# design.net
KiCad netlist of a schematic drawn in Altium Designer
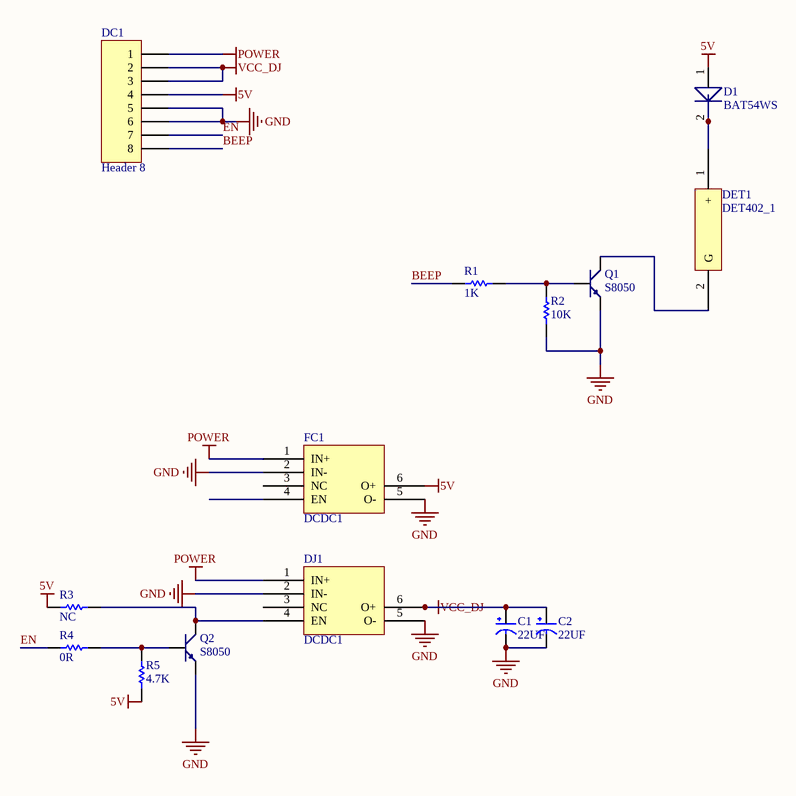
[diagram p0: 供电模块.SchDoc]

(export (version "E")
  (design (tool "Eeschema 10.0.6"))
  (components
    (comp (ref "C1")
      (value "22UF")
      (footprint "C0603")
      (description "胆电容")
      (libsource (lib "stm32f429i") (part "CAP1"))
    )
    (comp (ref "C2")
      (value "22UF")
      (footprint "C0603")
      (description "胆电容")
      (libsource (lib "stm32f429i") (part "CAP1"))
    )
    (comp (ref "D1")
      (value "BAT54WS")
      (footprint "SOD-323")
      (description "单肖特基二极管")
      (libsource (lib "MiniFly ") (part "BAT54"))
    )
    (comp (ref "DC1")
      (value "Header 8")
      (footprint "HDR1X8")
      (description "Header, 8-Pin")
      (fields (field (name "PUBLISHER") "Altium Limited"))
      (libsource (lib "Miscellaneous Connectors") (part "Header 8"))
    )
    (comp (ref "DET1") (value "DET402_1") (footprint "BEEP") (libsource (lib "EXPLORER") (part "DET402_1")))
    (comp (ref "DJ1") (value "DCDC1") (footprint "DCDC1") (libsource (lib "EXPLORER") (part "DCDC1")))
    (comp (ref "FC1") (value "DCDC1") (footprint "DCDC1") (libsource (lib "EXPLORER") (part "DCDC1")))
    (comp (ref "Q1")
      (value "S8050")
      (footprint "SOT-23R")
      (description "8050/BCW846/BCW847")
      (libsource (lib "EXPLORER") (part "NPN"))
    )
    (comp (ref "Q2")
      (value "S8050")
      (footprint "SOT-23R")
      (description "8050/BCW846/BCW847")
      (libsource (lib "EXPLORER") (part "NPN"))
    )
    (comp (ref "R1")
      (value "1K")
      (footprint "R0603")
      (description "0603")
      (libsource (lib "stm32f429i") (part "Res2"))
    )
    (comp (ref "R2")
      (value "10K")
      (footprint "R0603")
      (description "0603")
      (libsource (lib "stm32f429i") (part "Res2"))
    )
    (comp (ref "R3")
      (value "NC")
      (footprint "R0805")
      (description "0603")
      (libsource (lib "stm32f429i") (part "Res2"))
    )
    (comp (ref "R4")
      (value "0R")
      (footprint "R0603")
      (description "0603")
      (libsource (lib "stm32f429i") (part "Res2"))
    )
    (comp (ref "R5")
      (value "4.7K")
      (footprint "R0603")
      (description "0603")
      (libsource (lib "stm32f429i") (part "Res2"))
    )
  )
  (nets
    (net (code "1") (name "/BEEP") (class "Default")
      (node (ref "DC1") (pin "8") (pinfunction "8_8") (pintype "passive"))
      (node (ref "R1") (pin "2") (pinfunction "2_2") (pintype "passive"))
    )
    (net (code "2") (name "/EN") (class "Default")
      (node (ref "DC1") (pin "7") (pinfunction "7_7") (pintype "passive"))
      (node (ref "R4") (pin "2") (pinfunction "2_2") (pintype "passive"))
    )
    (net (code "3") (name "5V") (class "Default")
      (node (ref "D1") (pin "1") (pinfunction "1_1") (pintype "passive"))
      (node (ref "DC1") (pin "4") (pinfunction "4_4") (pintype "passive"))
      (node (ref "FC1") (pin "6") (pinfunction "O+_6") (pintype "passive"))
      (node (ref "R3") (pin "2") (pinfunction "2_2") (pintype "passive"))
      (node (ref "R5") (pin "1") (pinfunction "1_1") (pintype "passive"))
    )
    (net (code "4") (name "GND") (class "Default")
      (node (ref "C1") (pin "2") (pinfunction "GND_2") (pintype "passive"))
      (node (ref "C2") (pin "2") (pinfunction "GND_2") (pintype "passive"))
      (node (ref "DC1") (pin "5") (pinfunction "5_5") (pintype "passive"))
      (node (ref "DC1") (pin "6") (pinfunction "6_6") (pintype "passive"))
      (node (ref "DJ1") (pin "2") (pinfunction "IN-_2") (pintype "passive"))
      (node (ref "DJ1") (pin "5") (pinfunction "O-_5") (pintype "passive"))
      (node (ref "FC1") (pin "2") (pinfunction "IN-_2") (pintype "passive"))
      (node (ref "FC1") (pin "5") (pinfunction "O-_5") (pintype "passive"))
      (node (ref "Q1") (pin "1") (pinfunction "E_1") (pintype "passive"))
      (node (ref "Q2") (pin "1") (pinfunction "E_1") (pintype "passive"))
      (node (ref "R2") (pin "1") (pinfunction "1_1") (pintype "passive"))
    )
    (net (code "5") (name "Net-(DET1-+)") (class "Default")
      (node (ref "D1") (pin "2") (pinfunction "2_2") (pintype "passive"))
      (node (ref "DET1") (pin "1") (pinfunction "+_1") (pintype "passive"))
    )
    (net (code "6") (name "Net-(DET1-G)") (class "Default")
      (node (ref "DET1") (pin "2") (pinfunction "G_2") (pintype "passive"))
      (node (ref "Q1") (pin "3") (pinfunction "C_3") (pintype "passive"))
    )
    (net (code "7") (name "Net-(DJ1-EN)") (class "Default")
      (node (ref "DJ1") (pin "4") (pinfunction "EN_4") (pintype "passive"))
      (node (ref "Q2") (pin "3") (pinfunction "C_3") (pintype "passive"))
      (node (ref "R3") (pin "1") (pinfunction "1_1") (pintype "passive"))
    )
    (net (code "8") (name "Net-(Q1-B)") (class "Default")
      (node (ref "Q1") (pin "2") (pinfunction "B_2") (pintype "passive"))
      (node (ref "R1") (pin "1") (pinfunction "1_1") (pintype "passive"))
      (node (ref "R2") (pin "2") (pinfunction "2_2") (pintype "passive"))
    )
    (net (code "9") (name "Net-(Q2-B)") (class "Default")
      (node (ref "Q2") (pin "2") (pinfunction "B_2") (pintype "passive"))
      (node (ref "R4") (pin "1") (pinfunction "1_1") (pintype "passive"))
      (node (ref "R5") (pin "2") (pinfunction "2_2") (pintype "passive"))
    )
    (net (code "10") (name "POWER") (class "Default")
      (node (ref "DC1") (pin "1") (pinfunction "1_1") (pintype "passive"))
      (node (ref "DJ1") (pin "1") (pinfunction "IN+_1") (pintype "passive"))
      (node (ref "FC1") (pin "1") (pinfunction "IN+_1") (pintype "passive"))
    )
    (net (code "11") (name "VCC_DJ") (class "Default")
      (node (ref "C1") (pin "1") (pinfunction "VCC_1") (pintype "passive"))
      (node (ref "C2") (pin "1") (pinfunction "VCC_1") (pintype "passive"))
      (node (ref "DC1") (pin "2") (pinfunction "2_2") (pintype "passive"))
      (node (ref "DC1") (pin "3") (pinfunction "3_3") (pintype "passive"))
      (node (ref "DJ1") (pin "6") (pinfunction "O+_6") (pintype "passive"))
    )
    (net (code "12") (name "unconnected-(DJ1-NC-Pad3)") (class "Default")
      (node (ref "DJ1") (pin "3") (pinfunction "NC_3") (pintype "passive"))
    )
    (net (code "13") (name "unconnected-(FC1-EN-Pad4)") (class "Default")
      (node (ref "FC1") (pin "4") (pinfunction "EN_4") (pintype "passive"))
    )
    (net (code "14") (name "unconnected-(FC1-NC-Pad3)") (class "Default")
      (node (ref "FC1") (pin "3") (pinfunction "NC_3") (pintype "passive"))
    )
  )
)
